# board_4.net
KiCad netlist of a schematic drawn in EAGLE
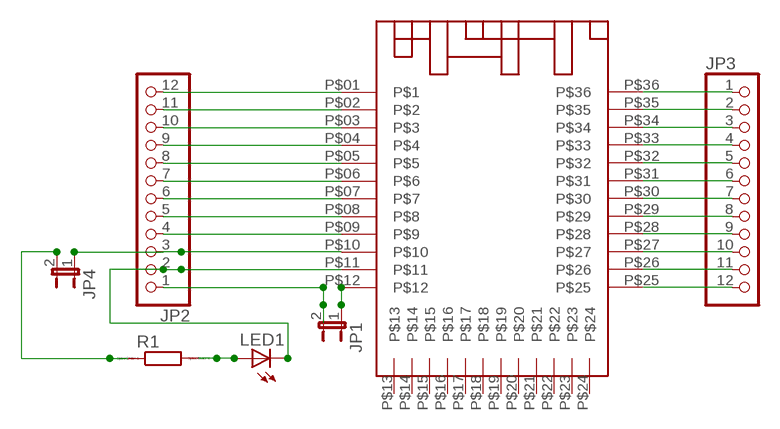
[diagram p0: schematic, sheet 1]

(export (version "E")
  (design (tool "Eeschema 10.0.6"))
  (components
    (comp (ref "JP1")
      (value "JP1E")
      (footprint "eagle-import:JP1")
      (libsource (lib "eagle-import") (part "JP1E"))
    )
    (comp (ref "JP2")
      (value "PINHD-1X12")
      (footprint "eagle-import:1X12")
      (libsource (lib "eagle-import") (part "PINHD-1X12"))
    )
    (comp (ref "JP3")
      (value "PINHD-1X12")
      (footprint "eagle-import:1X12")
      (libsource (lib "eagle-import") (part "PINHD-1X12"))
    )
    (comp (ref "JP4")
      (value "JP1E")
      (footprint "eagle-import:JP1")
      (libsource (lib "eagle-import") (part "JP1E"))
    )
    (comp (ref "LED1")
      (value "LED5MM")
      (footprint "eagle-import:LED5MM")
      (libsource (lib "eagle-import") (part "LED5MM"))
    )
    (comp (ref "R1")
      (value "R0207/10")
      (footprint "eagle-import:0207_10")
      (libsource (lib "eagle-import") (part "R0207/10"))
    )
    (comp (ref "U$1")
      (value "HZX_MODULE")
      (footprint "eagle-import:SMD_PAD_VERSION")
      (fields (field (name "AUTHOR") "Agam"))
      (libsource (lib "eagle-import") (part "HZX_MODULE"))
    )
  )
  (nets
    (net (code "1") (name "Net-(JP1-Pad1)") (class "Default")
      (node (ref "JP1") (pin "1") (pinfunction "1_1") (pintype "passive"))
      (node (ref "U$1") (pin "P$12") (pinfunction "P$12_P$12") (pintype "bidirectional"))
    )
    (net (code "2") (name "Net-(JP1-Pad2)") (class "Default")
      (node (ref "JP1") (pin "2") (pinfunction "2_2") (pintype "passive"))
      (node (ref "JP2") (pin "1") (pinfunction "1_1") (pintype "passive"))
    )
    (net (code "3") (name "Net-(JP2-Pad3)") (class "Default")
      (node (ref "JP2") (pin "3") (pinfunction "3_3") (pintype "passive"))
      (node (ref "JP4") (pin "1") (pinfunction "1_1") (pintype "passive"))
      (node (ref "U$1") (pin "P$10") (pinfunction "P$10_P$10") (pintype "bidirectional"))
    )
    (net (code "4") (name "Net-(JP3-Pad1)") (class "Default")
      (node (ref "JP3") (pin "1") (pinfunction "1_1") (pintype "passive"))
      (node (ref "U$1") (pin "P$36") (pinfunction "P$36_P$36") (pintype "bidirectional"))
    )
    (net (code "5") (name "Net-(JP3-Pad2)") (class "Default")
      (node (ref "JP3") (pin "2") (pinfunction "2_2") (pintype "passive"))
      (node (ref "U$1") (pin "P$35") (pinfunction "P$35_P$35") (pintype "bidirectional"))
    )
    (net (code "6") (name "Net-(JP3-Pad3)") (class "Default")
      (node (ref "JP3") (pin "3") (pinfunction "3_3") (pintype "passive"))
      (node (ref "U$1") (pin "P$34") (pinfunction "P$34_P$34") (pintype "bidirectional"))
    )
    (net (code "7") (name "Net-(JP3-Pad4)") (class "Default")
      (node (ref "JP3") (pin "4") (pinfunction "4_4") (pintype "passive"))
      (node (ref "U$1") (pin "P$33") (pinfunction "P$33_P$33") (pintype "bidirectional"))
    )
    (net (code "8") (name "Net-(JP3-Pad5)") (class "Default")
      (node (ref "JP3") (pin "5") (pinfunction "5_5") (pintype "passive"))
      (node (ref "U$1") (pin "P$32") (pinfunction "P$32_P$32") (pintype "bidirectional"))
    )
    (net (code "9") (name "Net-(JP3-Pad6)") (class "Default")
      (node (ref "JP3") (pin "6") (pinfunction "6_6") (pintype "passive"))
      (node (ref "U$1") (pin "P$31") (pinfunction "P$31_P$31") (pintype "bidirectional"))
    )
    (net (code "10") (name "Net-(JP3-Pad7)") (class "Default")
      (node (ref "JP3") (pin "7") (pinfunction "7_7") (pintype "passive"))
      (node (ref "U$1") (pin "P$30") (pinfunction "P$30_P$30") (pintype "bidirectional"))
    )
    (net (code "11") (name "Net-(JP3-Pad8)") (class "Default")
      (node (ref "JP3") (pin "8") (pinfunction "8_8") (pintype "passive"))
      (node (ref "U$1") (pin "P$29") (pinfunction "P$29_P$29") (pintype "bidirectional"))
    )
    (net (code "12") (name "Net-(JP3-Pad9)") (class "Default")
      (node (ref "JP3") (pin "9") (pinfunction "9_9") (pintype "passive"))
      (node (ref "U$1") (pin "P$28") (pinfunction "P$28_P$28") (pintype "bidirectional"))
    )
    (net (code "13") (name "Net-(JP3-Pad10)") (class "Default")
      (node (ref "JP3") (pin "10") (pinfunction "10_10") (pintype "passive"))
      (node (ref "U$1") (pin "P$27") (pinfunction "P$27_P$27") (pintype "bidirectional"))
    )
    (net (code "14") (name "Net-(JP3-Pad11)") (class "Default")
      (node (ref "JP3") (pin "11") (pinfunction "11_11") (pintype "passive"))
      (node (ref "U$1") (pin "P$26") (pinfunction "P$26_P$26") (pintype "bidirectional"))
    )
    (net (code "15") (name "Net-(JP3-Pad12)") (class "Default")
      (node (ref "JP3") (pin "12") (pinfunction "12_12") (pintype "passive"))
      (node (ref "U$1") (pin "P$25") (pinfunction "P$25_P$25") (pintype "bidirectional"))
    )
    (net (code "16") (name "Net-(JP4-Pad2)") (class "Default")
      (node (ref "JP4") (pin "2") (pinfunction "2_2") (pintype "passive"))
      (node (ref "R1") (pin "1") (pinfunction "1_1") (pintype "passive"))
    )
    (net (code "17") (name "Net-(LED1-C)") (class "Default")
      (node (ref "JP2") (pin "2") (pinfunction "2_2") (pintype "passive"))
      (node (ref "LED1") (pin "K") (pinfunction "C_K") (pintype "passive"))
      (node (ref "U$1") (pin "P$11") (pinfunction "P$11_P$11") (pintype "bidirectional"))
    )
    (net (code "18") (name "Net-(LED1-PadA)") (class "Default")
      (node (ref "LED1") (pin "A") (pinfunction "A_A") (pintype "passive"))
      (node (ref "R1") (pin "2") (pinfunction "2_2") (pintype "passive"))
    )
    (net (code "19") (name "Net-(U$1-P$1)") (class "Default")
      (node (ref "JP2") (pin "12") (pinfunction "12_12") (pintype "passive"))
      (node (ref "U$1") (pin "P$01") (pinfunction "P$1_P$01") (pintype "bidirectional"))
    )
    (net (code "20") (name "Net-(U$1-P$2)") (class "Default")
      (node (ref "JP2") (pin "11") (pinfunction "11_11") (pintype "passive"))
      (node (ref "U$1") (pin "P$02") (pinfunction "P$2_P$02") (pintype "bidirectional"))
    )
    (net (code "21") (name "Net-(U$1-P$3)") (class "Default")
      (node (ref "JP2") (pin "10") (pinfunction "10_10") (pintype "passive"))
      (node (ref "U$1") (pin "P$03") (pinfunction "P$3_P$03") (pintype "bidirectional"))
    )
    (net (code "22") (name "Net-(U$1-P$4)") (class "Default")
      (node (ref "JP2") (pin "9") (pinfunction "9_9") (pintype "passive"))
      (node (ref "U$1") (pin "P$04") (pinfunction "P$4_P$04") (pintype "bidirectional"))
    )
    (net (code "23") (name "Net-(U$1-P$5)") (class "Default")
      (node (ref "JP2") (pin "8") (pinfunction "8_8") (pintype "passive"))
      (node (ref "U$1") (pin "P$05") (pinfunction "P$5_P$05") (pintype "bidirectional"))
    )
    (net (code "24") (name "Net-(U$1-P$6)") (class "Default")
      (node (ref "JP2") (pin "7") (pinfunction "7_7") (pintype "passive"))
      (node (ref "U$1") (pin "P$06") (pinfunction "P$6_P$06") (pintype "bidirectional"))
    )
    (net (code "25") (name "Net-(U$1-P$7)") (class "Default")
      (node (ref "JP2") (pin "6") (pinfunction "6_6") (pintype "passive"))
      (node (ref "U$1") (pin "P$07") (pinfunction "P$7_P$07") (pintype "bidirectional"))
    )
    (net (code "26") (name "Net-(U$1-P$8)") (class "Default")
      (node (ref "JP2") (pin "5") (pinfunction "5_5") (pintype "passive"))
      (node (ref "U$1") (pin "P$08") (pinfunction "P$8_P$08") (pintype "bidirectional"))
    )
    (net (code "27") (name "Net-(U$1-P$9)") (class "Default")
      (node (ref "JP2") (pin "4") (pinfunction "4_4") (pintype "passive"))
      (node (ref "U$1") (pin "P$09") (pinfunction "P$9_P$09") (pintype "bidirectional"))
    )
    (net (code "28") (name "unconnected-(U$1-PadP$13)") (class "Default")
      (node (ref "U$1") (pin "P$13") (pinfunction "P$13_P$13") (pintype "bidirectional"))
    )
    (net (code "29") (name "unconnected-(U$1-PadP$14)") (class "Default")
      (node (ref "U$1") (pin "P$14") (pinfunction "P$14_P$14") (pintype "bidirectional"))
    )
    (net (code "30") (name "unconnected-(U$1-PadP$15)") (class "Default")
      (node (ref "U$1") (pin "P$15") (pinfunction "P$15_P$15") (pintype "bidirectional"))
    )
    (net (code "31") (name "unconnected-(U$1-PadP$16)") (class "Default")
      (node (ref "U$1") (pin "P$16") (pinfunction "P$16_P$16") (pintype "bidirectional"))
    )
    (net (code "32") (name "unconnected-(U$1-PadP$17)") (class "Default")
      (node (ref "U$1") (pin "P$17") (pinfunction "P$17_P$17") (pintype "bidirectional"))
    )
    (net (code "33") (name "unconnected-(U$1-PadP$18)") (class "Default")
      (node (ref "U$1") (pin "P$18") (pinfunction "P$18_P$18") (pintype "bidirectional"))
    )
    (net (code "34") (name "unconnected-(U$1-PadP$19)") (class "Default")
      (node (ref "U$1") (pin "P$19") (pinfunction "P$19_P$19") (pintype "bidirectional"))
    )
    (net (code "35") (name "unconnected-(U$1-PadP$20)") (class "Default")
      (node (ref "U$1") (pin "P$20") (pinfunction "P$20_P$20") (pintype "bidirectional"))
    )
    (net (code "36") (name "unconnected-(U$1-PadP$21)") (class "Default")
      (node (ref "U$1") (pin "P$21") (pinfunction "P$21_P$21") (pintype "bidirectional"))
    )
    (net (code "37") (name "unconnected-(U$1-PadP$22)") (class "Default")
      (node (ref "U$1") (pin "P$22") (pinfunction "P$22_P$22") (pintype "bidirectional"))
    )
    (net (code "38") (name "unconnected-(U$1-PadP$23)") (class "Default")
      (node (ref "U$1") (pin "P$23") (pinfunction "P$23_P$23") (pintype "bidirectional"))
    )
    (net (code "39") (name "unconnected-(U$1-PadP$24)") (class "Default")
      (node (ref "U$1") (pin "P$24") (pinfunction "P$24_P$24") (pintype "bidirectional"))
    )
  )
)
